# sensor.net
KiCad netlist of a schematic drawn in Altium Designer
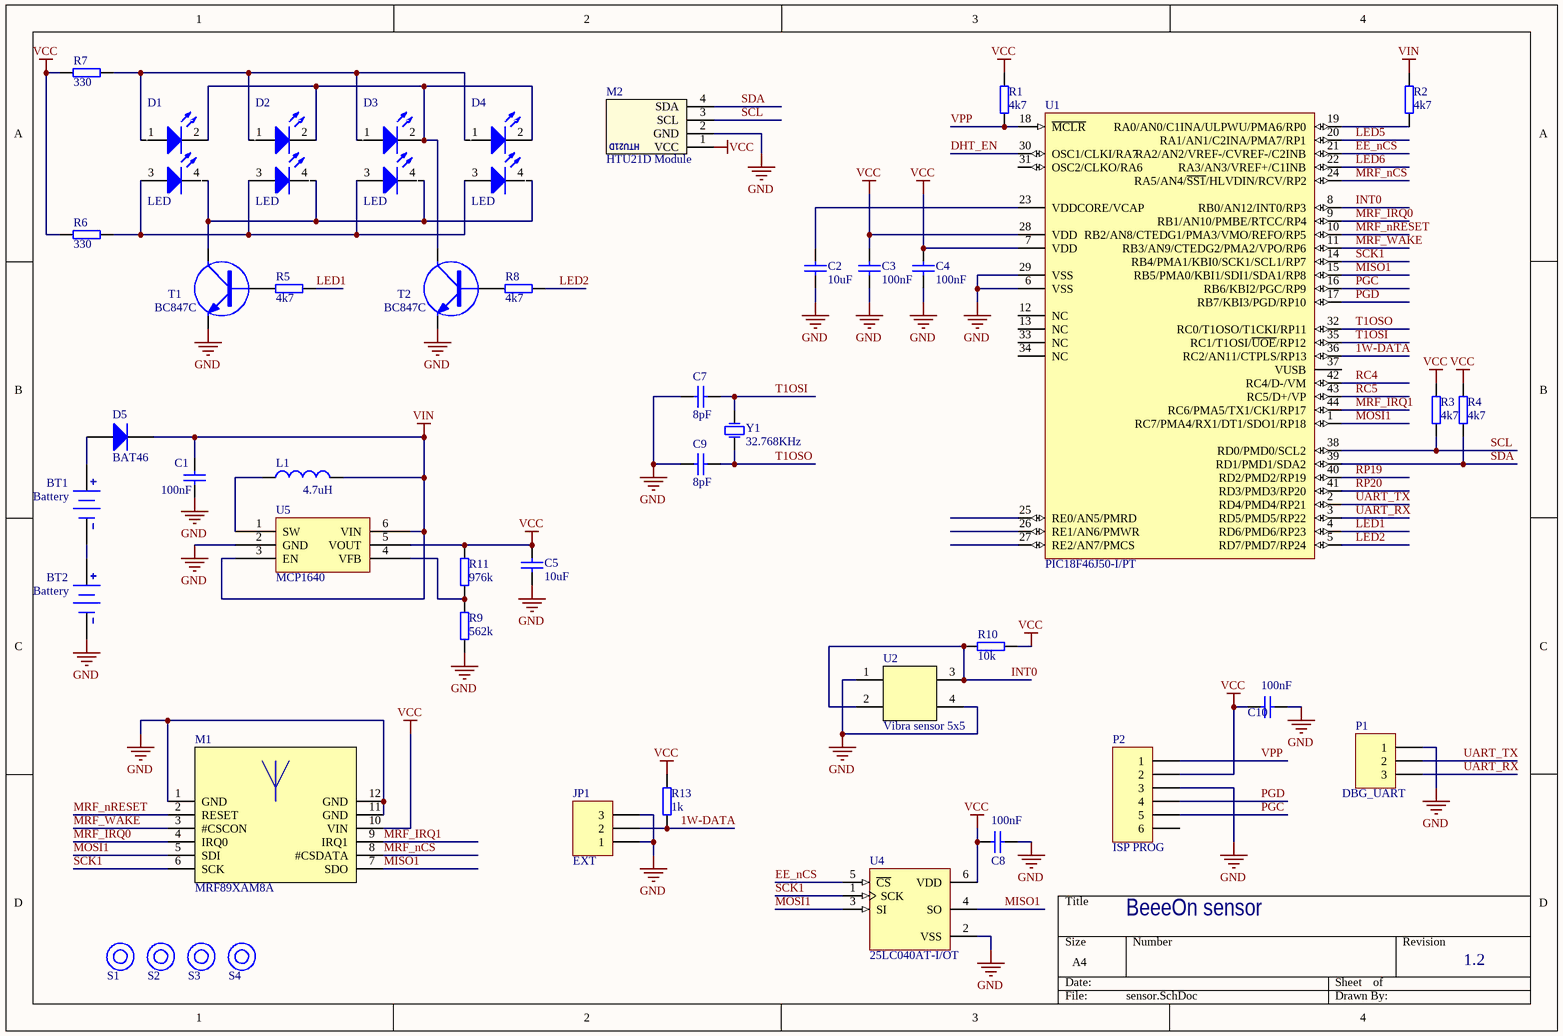
[diagram p0: sensor.SchDoc]

(export (version "E")
  (design (tool "Eeschema 10.0.6"))
  (components
    (comp (ref "BT1")
      (value "Battery")
      (footprint "BATT_HOLDER-AAA")
      (description "Multicell Battery")
      (fields (field (name "PUBLISHER") "Altium Limited"))
      (libsource (lib "ANY Devices") (part "Battery"))
    )
    (comp (ref "BT2")
      (value "Battery")
      (footprint "BATT_HOLDER-AAA")
      (description "Multicell Battery")
      (fields (field (name "PUBLISHER") "Altium Limited"))
      (libsource (lib "ANY Devices") (part "Battery"))
    )
    (comp (ref "C1")
      (value "100nF")
      (footprint "C0805")
      (description "Capacitor")
      (fields (field (name "PUBLISHER") "Altium Limited"))
      (libsource (lib "ANY Devices") (part "Cap"))
    )
    (comp (ref "C2")
      (value "10uF")
      (footprint "C0805")
      (description "Capacitor")
      (fields (field (name "PUBLISHER") "Altium Limited"))
      (libsource (lib "ANY Devices") (part "Cap"))
    )
    (comp (ref "C3")
      (value "100nF")
      (footprint "C0805")
      (description "Capacitor")
      (fields (field (name "PUBLISHER") "Altium Limited"))
      (libsource (lib "ANY Devices") (part "Cap"))
    )
    (comp (ref "C4")
      (value "100nF")
      (footprint "C0805")
      (description "Capacitor")
      (fields (field (name "PUBLISHER") "Altium Limited"))
      (libsource (lib "ANY Devices") (part "Cap"))
    )
    (comp (ref "C5")
      (value "10uF")
      (footprint "C0805")
      (description "Capacitor")
      (fields (field (name "PUBLISHER") "Altium Limited"))
      (libsource (lib "ANY Devices") (part "Cap"))
    )
    (comp (ref "C7")
      (value "8pF")
      (footprint "C0805")
      (description "Capacitor")
      (fields (field (name "PUBLISHER") "Altium Limited"))
      (libsource (lib "ANY Devices") (part "Cap"))
    )
    (comp (ref "C8")
      (value "100nF")
      (footprint "C0805")
      (description "Capacitor")
      (fields (field (name "PUBLISHER") "Altium Limited"))
      (libsource (lib "ANY Devices") (part "Cap"))
    )
    (comp (ref "C9")
      (value "8pF")
      (footprint "C0805")
      (description "Capacitor")
      (fields (field (name "PUBLISHER") "Altium Limited"))
      (libsource (lib "ANY Devices") (part "Cap"))
    )
    (comp (ref "C10")
      (value "100nF")
      (footprint "C0805")
      (description "Capacitor")
      (fields (field (name "PUBLISHER") "Altium Limited"))
      (libsource (lib "ANY Devices") (part "Cap"))
    )
    (comp (ref "D1")
      (value "LED")
      (footprint "LED MULTI2")
      (libsource (lib "ANY Devices") (part "LED MULT 2 S"))
    )
    (comp (ref "D2")
      (value "LED")
      (footprint "LED MULTI2")
      (libsource (lib "ANY Devices") (part "LED MULT 2 S"))
    )
    (comp (ref "D3")
      (value "LED")
      (footprint "LED MULTI2")
      (libsource (lib "ANY Devices") (part "LED MULT 2 S"))
    )
    (comp (ref "D4")
      (value "LED")
      (footprint "LED MULTI2")
      (libsource (lib "ANY Devices") (part "LED MULT 2 S"))
    )
    (comp (ref "D5")
      (value "BAT46")
      (footprint "SOD-323")
      (description "Default Diode")
      (fields (field (name "PUBLISHER") "Altium Limited"))
      (libsource (lib "ANY Devices") (part "Diode"))
    )
    (comp (ref "JP1")
      (value "EXT")
      (footprint "HDR1X3H")
      (description "Header, 3-Pin, Right Angle")
      (fields (field (name "PUBLISHER") "Altium Limited"))
      (libsource (lib "ANY Connectors") (part "Header 3H"))
    )
    (comp (ref "L1")
      (value "4.7uH")
      (footprint "IND3x3")
      (description "Inductor")
      (fields (field (name "PUBLISHER") "Altium Limited"))
      (libsource (lib "ANY Devices") (part "Inductor"))
    )
    (comp (ref "M1")
      (value "MRF89XAM8A")
      (footprint "MRF89XAM8A")
      (description "868 MHz Ultra-Low Power  Sub-GHz Transceiver Module")
      (libsource (lib "Modules") (part "MRF89XAM8A"))
    )
    (comp (ref "M2")
      (value "HTU21D Module")
      (footprint "HTU21D")
      (description "Digital Barometric Pressure Sensor Module")
      (libsource (lib "Modules") (part "HTU21D_MODULE"))
    )
    (comp (ref "P1")
      (value "DBG_UART")
      (footprint "HDR1X3")
      (description "Header, 3-Pin")
      (fields (field (name "PUBLISHER") "Altium Limited"))
      (libsource (lib "ANY Connectors") (part "Header 3"))
    )
    (comp (ref "P2")
      (value "ISP PROG")
      (footprint "HDR1X6")
      (description "Header, 6-Pin")
      (fields (field (name "PUBLISHER") "Altium Limited"))
      (libsource (lib "ANY Connectors") (part "Header 6"))
    )
    (comp (ref "R1")
      (value "4k7")
      (footprint "R0805")
      (description "Resistor")
      (fields (field (name "PUBLISHER") "Altium Limited"))
      (libsource (lib "ANY Devices") (part "Res2"))
    )
    (comp (ref "R2")
      (value "4k7")
      (footprint "R0805")
      (description "Resistor")
      (fields (field (name "PUBLISHER") "Altium Limited"))
      (libsource (lib "") (part "Res2_1"))
    )
    (comp (ref "R3")
      (value "4k7")
      (footprint "R0805")
      (description "Resistor")
      (fields (field (name "PUBLISHER") "Altium Limited"))
      (libsource (lib "ANY Devices") (part "Res2"))
    )
    (comp (ref "R4")
      (value "4k7")
      (footprint "R0805")
      (description "Resistor")
      (fields (field (name "PUBLISHER") "Altium Limited"))
      (libsource (lib "ANY Devices") (part "Res2"))
    )
    (comp (ref "R5")
      (value "4k7")
      (footprint "R0805")
      (description "Resistor")
      (fields (field (name "PUBLISHER") "Altium Limited"))
      (libsource (lib "") (part "Res2_2"))
    )
    (comp (ref "R6")
      (value "330")
      (footprint "R0805")
      (description "Resistor")
      (fields (field (name "PUBLISHER") "Altium Limited"))
      (libsource (lib "") (part "Res2_3"))
    )
    (comp (ref "R7")
      (value "330")
      (footprint "R0805")
      (description "Resistor")
      (fields (field (name "PUBLISHER") "Altium Limited"))
      (libsource (lib "") (part "Res2_3"))
    )
    (comp (ref "R8")
      (value "4k7")
      (footprint "R0805")
      (description "Resistor")
      (fields (field (name "PUBLISHER") "Altium Limited"))
      (libsource (lib "") (part "Res2_2"))
    )
    (comp (ref "R9")
      (value "562k")
      (footprint "R0805")
      (description "Resistor")
      (fields (field (name "PUBLISHER") "Altium Limited"))
      (libsource (lib "") (part "Res2_1"))
    )
    (comp (ref "R10")
      (value "10k")
      (footprint "R0805")
      (description "Resistor")
      (fields (field (name "PUBLISHER") "Altium Limited"))
      (libsource (lib "") (part "Res2_2"))
    )
    (comp (ref "R11")
      (value "976k")
      (footprint "R0805")
      (description "Resistor")
      (fields (field (name "PUBLISHER") "Altium Limited"))
      (libsource (lib "") (part "Res2_1"))
    )
    (comp (ref "R13")
      (value "1k")
      (footprint "R0805")
      (description "Resistor")
      (fields (field (name "PUBLISHER") "Altium Limited"))
      (libsource (lib "") (part "Res2_1"))
    )
    (comp (ref "S1") (value "TARGET") (footprint "TARGET") (libsource (lib "ANY Devices") (part "TARGET")))
    (comp (ref "S2") (value "TARGET") (footprint "TARGET") (libsource (lib "ANY Devices") (part "TARGET")))
    (comp (ref "S3") (value "TARGET") (footprint "TARGET") (libsource (lib "ANY Devices") (part "TARGET")))
    (comp (ref "S4") (value "TARGET") (footprint "TARGET") (libsource (lib "ANY Devices") (part "TARGET")))
    (comp (ref "T1")
      (value "BC847C")
      (footprint "SOT23")
      (description "NPN General-purpose Transistor")
      (fields (field (name "PUBLISHER") "Altium Limited"))
      (libsource (lib "ANY Devices") (part "NPN_BC847C"))
    )
    (comp (ref "T2")
      (value "BC847C")
      (footprint "SOT23")
      (description "NPN General-purpose Transistor")
      (fields (field (name "PUBLISHER") "Altium Limited"))
      (libsource (lib "ANY Devices") (part "NPN_BC847C"))
    )
    (comp (ref "U1")
      (value "PIC18F46J50-I/PT")
      (footprint "TQFP-PT44_N")
      (fields (field (name "PUBLISHER") "Altium Limited"))
      (libsource (lib "ANY Devices") (part "PIC18F46J50-I/PT"))
    )
    (comp (ref "U2")
      (value "Vibra sensor 5x5")
      (footprint "VIBRATION_SENSOR 5x5")
      (description "Vibration sensor 5x5")
      (libsource (lib "ANY Devices") (part "Vibra sensor"))
    )
    (comp (ref "U4")
      (value "25LC040AT-I/OT")
      (footprint "SOT-23-OT6_N")
      (description "4K SPI Bus Serial EEPROM, 6-Pin SOT-23, Industrial Temperature, Tape and Reel")
      (fields (field (name "PUBLISHER") "Altium Limited"))
      (libsource (lib "ANYlib") (part "25LC040AT-I/OT"))
    )
    (comp (ref "U5")
      (value "MCP1640")
      (footprint "SOT-23-OT6_N")
      (description "0.65V Start-up Synchronous Boost Regulator")
      (libsource (lib "ANYlib") (part "MCP1640"))
    )
    (comp (ref "Y1")
      (value "32.768KHz")
      (footprint "R38")
      (description "Crystal Oscillator")
      (fields (field (name "PUBLISHER") "Altium Limited"))
      (libsource (lib "ANY Devices") (part "XTAL"))
    )
  )
  (nets
    (net (code "1") (name "/1W-DATA") (class "Default")
      (node (ref "JP1") (pin "2") (pinfunction "2_2") (pintype "passive"))
      (node (ref "R13") (pin "2") (pinfunction "2_2") (pintype "passive"))
      (node (ref "U1") (pin "36") (pinfunction "RC2/AN11/CTPLS/RP13_36") (pintype "bidirectional"))
    )
    (net (code "2") (name "/DHT_EN") (class "Default")
      (node (ref "U1") (pin "30") (pinfunction "OSC1/CLKI/RA7_30") (pintype "bidirectional"))
    )
    (net (code "3") (name "/EE_nCS") (class "Default")
      (node (ref "U1") (pin "21") (pinfunction "RA2/AN2/VREF-/CVREF-/C2INB_21") (pintype "bidirectional"))
      (node (ref "U4") (pin "5") (pinfunction "~{CS}_5") (pintype "input"))
    )
    (net (code "4") (name "/INT0") (class "Default")
      (node (ref "R10") (pin "2") (pinfunction "2_2") (pintype "passive"))
      (node (ref "U1") (pin "8") (pinfunction "RB0/AN12/INT0/RP3_8") (pintype "bidirectional"))
      (node (ref "U2") (pin "2") (pintype "passive"))
      (node (ref "U2") (pin "3") (pintype "passive"))
    )
    (net (code "5") (name "/LED1") (class "Default")
      (node (ref "R5") (pin "1") (pinfunction "1_1") (pintype "passive"))
      (node (ref "U1") (pin "4") (pinfunction "RD6/PMD6/RP23_4") (pintype "bidirectional"))
    )
    (net (code "6") (name "/LED2") (class "Default")
      (node (ref "R8") (pin "1") (pinfunction "1_1") (pintype "passive"))
      (node (ref "U1") (pin "5") (pinfunction "RD7/PMD7/RP24_5") (pintype "bidirectional"))
    )
    (net (code "7") (name "/LED5") (class "Default")
      (node (ref "U1") (pin "20") (pinfunction "RA1/AN1/C2INA/PMA7/RP1_20") (pintype "bidirectional"))
    )
    (net (code "8") (name "/LED6") (class "Default")
      (node (ref "U1") (pin "22") (pinfunction "RA3/AN3/VREF+/C1INB_22") (pintype "bidirectional"))
    )
    (net (code "9") (name "/MISO1") (class "Default")
      (node (ref "M1") (pin "7") (pinfunction "SDO_7") (pintype "passive"))
      (node (ref "U1") (pin "15") (pinfunction "RB5/PMA0/KBI1/SDI1/SDA1/RP8_15") (pintype "bidirectional"))
      (node (ref "U4") (pin "4") (pinfunction "SO_4") (pintype "tri_state"))
    )
    (net (code "10") (name "/MOSI1") (class "Default")
      (node (ref "M1") (pin "5") (pinfunction "SDI_5") (pintype "passive"))
      (node (ref "U1") (pin "1") (pinfunction "RC7/PMA4/RX1/DT1/SDO1/RP18_1") (pintype "bidirectional"))
      (node (ref "U4") (pin "3") (pinfunction "SI_3") (pintype "input"))
    )
    (net (code "11") (name "/MRF_IRQ0") (class "Default")
      (node (ref "M1") (pin "4") (pinfunction "IRQ0_4") (pintype "passive"))
      (node (ref "U1") (pin "9") (pinfunction "RB1/AN10/PMBE/RTCC/RP4_9") (pintype "bidirectional"))
    )
    (net (code "12") (name "/MRF_IRQ1") (class "Default")
      (node (ref "M1") (pin "9") (pinfunction "IRQ1_9") (pintype "passive"))
      (node (ref "U1") (pin "44") (pinfunction "RC6/PMA5/TX1/CK1/RP17_44") (pintype "bidirectional"))
    )
    (net (code "13") (name "/MRF_WAKE") (class "Default")
      (node (ref "M1") (pin "3") (pinfunction "#CSCON_3") (pintype "passive"))
      (node (ref "U1") (pin "11") (pinfunction "RB3/AN9/CTEDG2/PMA2/VPO/RP6_11") (pintype "bidirectional"))
    )
    (net (code "14") (name "/MRF_nCS") (class "Default")
      (node (ref "M1") (pin "8") (pinfunction "#CSDATA_8") (pintype "passive"))
      (node (ref "U1") (pin "24") (pinfunction "RA5/AN4/~{SS1}/HLVDIN/RCV/RP2_24") (pintype "bidirectional"))
    )
    (net (code "15") (name "/MRF_nRESET") (class "Default")
      (node (ref "M1") (pin "2") (pinfunction "RESET_2") (pintype "passive"))
      (node (ref "U1") (pin "10") (pinfunction "RB2/AN8/CTEDG1/PMA3/VMO/REFO/RP5_10") (pintype "bidirectional"))
    )
    (net (code "16") (name "/PGC") (class "Default")
      (node (ref "P2") (pin "5") (pinfunction "5_5") (pintype "passive"))
      (node (ref "U1") (pin "16") (pinfunction "RB6/KBI2/PGC/RP9_16") (pintype "bidirectional"))
    )
    (net (code "17") (name "/PGD") (class "Default")
      (node (ref "P2") (pin "4") (pinfunction "4_4") (pintype "passive"))
      (node (ref "U1") (pin "17") (pinfunction "RB7/KBI3/PGD/RP10_17") (pintype "bidirectional"))
    )
    (net (code "18") (name "/RC4") (class "Default")
      (node (ref "U1") (pin "42") (pinfunction "RC4/D-/VM_42") (pintype "bidirectional"))
    )
    (net (code "19") (name "/RC5") (class "Default")
      (node (ref "U1") (pin "43") (pinfunction "RC5/D+/VP_43") (pintype "bidirectional"))
    )
    (net (code "20") (name "/RP19") (class "Default")
      (node (ref "U1") (pin "40") (pinfunction "RD2/PMD2/RP19_40") (pintype "bidirectional"))
    )
    (net (code "21") (name "/RP20") (class "Default")
      (node (ref "U1") (pin "41") (pinfunction "RD3/PMD3/RP20_41") (pintype "bidirectional"))
    )
    (net (code "22") (name "/SCK1") (class "Default")
      (node (ref "M1") (pin "6") (pinfunction "SCK_6") (pintype "passive"))
      (node (ref "U1") (pin "14") (pinfunction "RB4/PMA1/KBI0/SCK1/SCL1/RP7_14") (pintype "bidirectional"))
      (node (ref "U4") (pin "1") (pinfunction "SCK_1") (pintype "input"))
    )
    (net (code "23") (name "/SCL") (class "Default")
      (node (ref "M2") (pin "3") (pinfunction "SCL_3") (pintype "passive"))
      (node (ref "R3") (pin "1") (pinfunction "1_1") (pintype "passive"))
      (node (ref "U1") (pin "38") (pinfunction "RD0/PMD0/SCL2_38") (pintype "bidirectional"))
    )
    (net (code "24") (name "/SDA") (class "Default")
      (node (ref "M2") (pin "4") (pinfunction "SDA_4") (pintype "passive"))
      (node (ref "R4") (pin "1") (pinfunction "1_1") (pintype "passive"))
      (node (ref "U1") (pin "39") (pinfunction "RD1/PMD1/SDA2_39") (pintype "bidirectional"))
    )
    (net (code "25") (name "/T1OSI") (class "Default")
      (node (ref "C7") (pin "1") (pinfunction "1_1") (pintype "passive"))
      (node (ref "U1") (pin "35") (pinfunction "RC1/T1OSI/~{UOE}/RP12_35") (pintype "bidirectional"))
      (node (ref "Y1") (pin "2") (pinfunction "OSC2_2") (pintype "passive"))
    )
    (net (code "26") (name "/T1OSO") (class "Default")
      (node (ref "C9") (pin "1") (pinfunction "1_1") (pintype "passive"))
      (node (ref "U1") (pin "32") (pinfunction "RC0/T1OSO/T1CKI/RP11_32") (pintype "bidirectional"))
      (node (ref "Y1") (pin "1") (pinfunction "OSC1_1") (pintype "passive"))
    )
    (net (code "27") (name "/UART_RX") (class "Default")
      (node (ref "P1") (pin "3") (pinfunction "3_3") (pintype "passive"))
      (node (ref "U1") (pin "3") (pinfunction "RD5/PMD5/RP22_3") (pintype "bidirectional"))
    )
    (net (code "28") (name "/UART_TX") (class "Default")
      (node (ref "P1") (pin "2") (pinfunction "2_2") (pintype "passive"))
      (node (ref "U1") (pin "2") (pinfunction "RD4/PMD4/RP21_2") (pintype "bidirectional"))
    )
    (net (code "29") (name "/VPP") (class "Default")
      (node (ref "P2") (pin "1") (pinfunction "1_1") (pintype "passive"))
      (node (ref "R1") (pin "1") (pinfunction "1_1") (pintype "passive"))
      (node (ref "U1") (pin "18") (pinfunction "~{MCLR}_18") (pintype "input"))
    )
    (net (code "30") (name "GND") (class "Default")
      (node (ref "BT2") (pin "2") (pinfunction "-_2") (pintype "passive"))
      (node (ref "C1") (pin "1") (pinfunction "1_1") (pintype "passive"))
      (node (ref "C10") (pin "2") (pinfunction "2_2") (pintype "passive"))
      (node (ref "C2") (pin "2") (pinfunction "2_2") (pintype "passive"))
      (node (ref "C3") (pin "1") (pinfunction "1_1") (pintype "passive"))
      (node (ref "C4") (pin "2") (pinfunction "2_2") (pintype "passive"))
      (node (ref "C5") (pin "2") (pinfunction "2_2") (pintype "passive"))
      (node (ref "C7") (pin "2") (pinfunction "2_2") (pintype "passive"))
      (node (ref "C8") (pin "1") (pinfunction "1_1") (pintype "passive"))
      (node (ref "C9") (pin "2") (pinfunction "2_2") (pintype "passive"))
      (node (ref "JP1") (pin "1") (pinfunction "1_1") (pintype "passive"))
      (node (ref "JP1") (pin "3") (pinfunction "3_3") (pintype "passive"))
      (node (ref "M1") (pin "1") (pinfunction "GND_1") (pintype "passive"))
      (node (ref "M1") (pin "11") (pinfunction "GND_11") (pintype "passive"))
      (node (ref "M1") (pin "12") (pinfunction "GND_12") (pintype "passive"))
      (node (ref "M2") (pin "2") (pinfunction "GND_2") (pintype "passive"))
      (node (ref "P1") (pin "1") (pinfunction "1_1") (pintype "passive"))
      (node (ref "P2") (pin "3") (pinfunction "3_3") (pintype "passive"))
      (node (ref "R9") (pin "2") (pinfunction "2_2") (pintype "passive"))
      (node (ref "T1") (pin "2") (pinfunction "E_2") (pintype "passive"))
      (node (ref "T2") (pin "2") (pinfunction "E_2") (pintype "passive"))
      (node (ref "U1") (pin "29") (pinfunction "VSS_29") (pintype "power_in"))
      (node (ref "U1") (pin "6") (pinfunction "VSS_6") (pintype "power_in"))
      (node (ref "U2") (pin "1") (pintype "passive"))
      (node (ref "U2") (pin "4") (pintype "passive"))
      (node (ref "U4") (pin "2") (pinfunction "VSS_2") (pintype "power_in"))
      (node (ref "U5") (pin "2") (pinfunction "GND_2") (pintype "passive"))
    )
    (net (code "31") (name "Net-(BT1-+)") (class "Default")
      (node (ref "BT1") (pin "1") (pinfunction "+_1") (pintype "passive"))
      (node (ref "D5") (pin "1") (pinfunction "A_1") (pintype "passive"))
    )
    (net (code "32") (name "Net-(BT1--)") (class "Default")
      (node (ref "BT1") (pin "2") (pinfunction "-_2") (pintype "passive"))
      (node (ref "BT2") (pin "1") (pinfunction "+_1") (pintype "passive"))
    )
    (net (code "33") (name "Net-(D1-A-Pad1)") (class "Default")
      (node (ref "D1") (pin "1") (pinfunction "A_1") (pintype "passive"))
      (node (ref "D2") (pin "1") (pinfunction "A_1") (pintype "passive"))
      (node (ref "D3") (pin "1") (pinfunction "A_1") (pintype "passive"))
      (node (ref "D4") (pin "1") (pinfunction "A_1") (pintype "passive"))
      (node (ref "R7") (pin "2") (pinfunction "2_2") (pintype "passive"))
    )
    (net (code "34") (name "Net-(D1-A-Pad3)") (class "Default")
      (node (ref "D1") (pin "3") (pinfunction "A_3") (pintype "passive"))
      (node (ref "D2") (pin "3") (pinfunction "A_3") (pintype "passive"))
      (node (ref "D3") (pin "3") (pinfunction "A_3") (pintype "passive"))
      (node (ref "D4") (pin "3") (pinfunction "A_3") (pintype "passive"))
      (node (ref "R6") (pin "2") (pinfunction "2_2") (pintype "passive"))
    )
    (net (code "35") (name "Net-(T1-B)") (class "Default")
      (node (ref "R5") (pin "2") (pinfunction "2_2") (pintype "passive"))
      (node (ref "T1") (pin "1") (pinfunction "B_1") (pintype "passive"))
    )
    (net (code "36") (name "Net-(T1-C)") (class "Default")
      (node (ref "D1") (pin "4") (pinfunction "K_4") (pintype "passive"))
      (node (ref "D2") (pin "4") (pinfunction "K_4") (pintype "passive"))
      (node (ref "D3") (pin "4") (pinfunction "K_4") (pintype "passive"))
      (node (ref "D4") (pin "4") (pinfunction "K_4") (pintype "passive"))
      (node (ref "T1") (pin "3") (pinfunction "C_3") (pintype "passive"))
    )
    (net (code "37") (name "Net-(T2-B)") (class "Default")
      (node (ref "R8") (pin "2") (pinfunction "2_2") (pintype "passive"))
      (node (ref "T2") (pin "1") (pinfunction "B_1") (pintype "passive"))
    )
    (net (code "38") (name "Net-(T2-C)") (class "Default")
      (node (ref "D1") (pin "2") (pinfunction "K_2") (pintype "passive"))
      (node (ref "D2") (pin "2") (pinfunction "K_2") (pintype "passive"))
      (node (ref "D3") (pin "2") (pinfunction "K_2") (pintype "passive"))
      (node (ref "D4") (pin "2") (pinfunction "K_2") (pintype "passive"))
      (node (ref "T2") (pin "3") (pinfunction "C_3") (pintype "passive"))
    )
    (net (code "39") (name "Net-(U1-RA0{slash}AN0{slash}C1INA{slash}ULPWU{slash}PMA6{slash}RP0)") (class "Default")
      (node (ref "R2") (pin "2") (pinfunction "2_2") (pintype "passive"))
      (node (ref "U1") (pin "19") (pinfunction "RA0/AN0/C1INA/ULPWU/PMA6/RP0_19") (pintype "bidirectional"))
    )
    (net (code "40") (name "Net-(U1-VDDCORE{slash}VCAP)") (class "Default")
      (node (ref "C2") (pin "1") (pinfunction "1_1") (pintype "passive"))
      (node (ref "U1") (pin "23") (pinfunction "VDDCORE/VCAP_23") (pintype "power_in"))
    )
    (net (code "41") (name "Net-(U5-SW)") (class "Default")
      (node (ref "L1") (pin "1") (pinfunction "1_1") (pintype "passive"))
      (node (ref "U5") (pin "1") (pinfunction "SW_1") (pintype "passive"))
    )
    (net (code "42") (name "Net-(U5-VFB)") (class "Default")
      (node (ref "R11") (pin "2") (pinfunction "2_2") (pintype "passive"))
      (node (ref "R9") (pin "1") (pinfunction "1_1") (pintype "passive"))
      (node (ref "U5") (pin "4") (pinfunction "VFB_4") (pintype "passive"))
    )
    (net (code "43") (name "VCC") (class "Default")
      (node (ref "C10") (pin "1") (pinfunction "1_1") (pintype "passive"))
      (node (ref "C3") (pin "2") (pinfunction "2_2") (pintype "passive"))
      (node (ref "C4") (pin "1") (pinfunction "1_1") (pintype "passive"))
      (node (ref "C5") (pin "1") (pinfunction "1_1") (pintype "passive"))
      (node (ref "C8") (pin "2") (pinfunction "2_2") (pintype "passive"))
      (node (ref "M1") (pin "10") (pinfunction "VIN_10") (pintype "passive"))
      (node (ref "M2") (pin "1") (pinfunction "VCC_1") (pintype "passive"))
      (node (ref "P2") (pin "2") (pinfunction "2_2") (pintype "passive"))
      (node (ref "R1") (pin "2") (pinfunction "2_2") (pintype "passive"))
      (node (ref "R10") (pin "1") (pinfunction "1_1") (pintype "passive"))
      (node (ref "R11") (pin "1") (pinfunction "1_1") (pintype "passive"))
      (node (ref "R13") (pin "1") (pinfunction "1_1") (pintype "passive"))
      (node (ref "R3") (pin "2") (pinfunction "2_2") (pintype "passive"))
      (node (ref "R4") (pin "2") (pinfunction "2_2") (pintype "passive"))
      (node (ref "R6") (pin "1") (pinfunction "1_1") (pintype "passive"))
      (node (ref "R7") (pin "1") (pinfunction "1_1") (pintype "passive"))
      (node (ref "U1") (pin "28") (pinfunction "VDD_28") (pintype "power_in"))
      (node (ref "U1") (pin "7") (pinfunction "VDD_7") (pintype "power_in"))
      (node (ref "U4") (pin "6") (pinfunction "VDD_6") (pintype "power_in"))
      (node (ref "U5") (pin "5") (pinfunction "VOUT_5") (pintype "passive"))
    )
    (net (code "44") (name "VIN") (class "Default")
      (node (ref "C1") (pin "2") (pinfunction "2_2") (pintype "passive"))
      (node (ref "D5") (pin "2") (pinfunction "K_2") (pintype "passive"))
      (node (ref "L1") (pin "2") (pinfunction "2_2") (pintype "passive"))
      (node (ref "R2") (pin "1") (pinfunction "1_1") (pintype "passive"))
      (node (ref "U5") (pin "3") (pinfunction "EN_3") (pintype "passive"))
      (node (ref "U5") (pin "6") (pinfunction "VIN_6") (pintype "passive"))
    )
    (net (code "45") (name "unconnected-(P2-Pad6)") (class "Default")
      (node (ref "P2") (pin "6") (pinfunction "6_6") (pintype "passive"))
    )
    (net (code "46") (name "unconnected-(U1-NC-Pad12)") (class "Default")
      (node (ref "U1") (pin "12") (pinfunction "NC_12") (pintype "passive"))
    )
    (net (code "47") (name "unconnected-(U1-NC-Pad13)") (class "Default")
      (node (ref "U1") (pin "13") (pinfunction "NC_13") (pintype "passive"))
    )
    (net (code "48") (name "unconnected-(U1-NC-Pad33)") (class "Default")
      (node (ref "U1") (pin "33") (pinfunction "NC_33") (pintype "passive"))
    )
    (net (code "49") (name "unconnected-(U1-NC-Pad34)") (class "Default")
      (node (ref "U1") (pin "34") (pinfunction "NC_34") (pintype "passive"))
    )
    (net (code "50") (name "unconnected-(U1-OSC2{slash}CLKO{slash}RA6-Pad31)") (class "Default")
      (node (ref "U1") (pin "31") (pinfunction "OSC2/CLKO/RA6_31") (pintype "bidirectional"))
    )
    (net (code "51") (name "unconnected-(U1-RE0{slash}AN5{slash}PMRD-Pad25)") (class "Default")
      (node (ref "U1") (pin "25") (pinfunction "RE0/AN5/PMRD_25") (pintype "bidirectional"))
    )
    (net (code "52") (name "unconnected-(U1-RE1{slash}AN6{slash}PMWR-Pad26)") (class "Default")
      (node (ref "U1") (pin "26") (pinfunction "RE1/AN6/PMWR_26") (pintype "bidirectional"))
    )
    (net (code "53") (name "unconnected-(U1-RE2{slash}AN7{slash}PMCS-Pad27)") (class "Default")
      (node (ref "U1") (pin "27") (pinfunction "RE2/AN7/PMCS_27") (pintype "bidirectional"))
    )
    (net (code "54") (name "unconnected-(U1-VUSB-Pad37)") (class "Default")
      (node (ref "U1") (pin "37") (pinfunction "VUSB_37") (pintype "power_in"))
    )
  )
)
